# SimpleFOCShieldV3_SchDoc_2024-06-23.net
KiCad netlist of a schematic drawn in Altium Designer
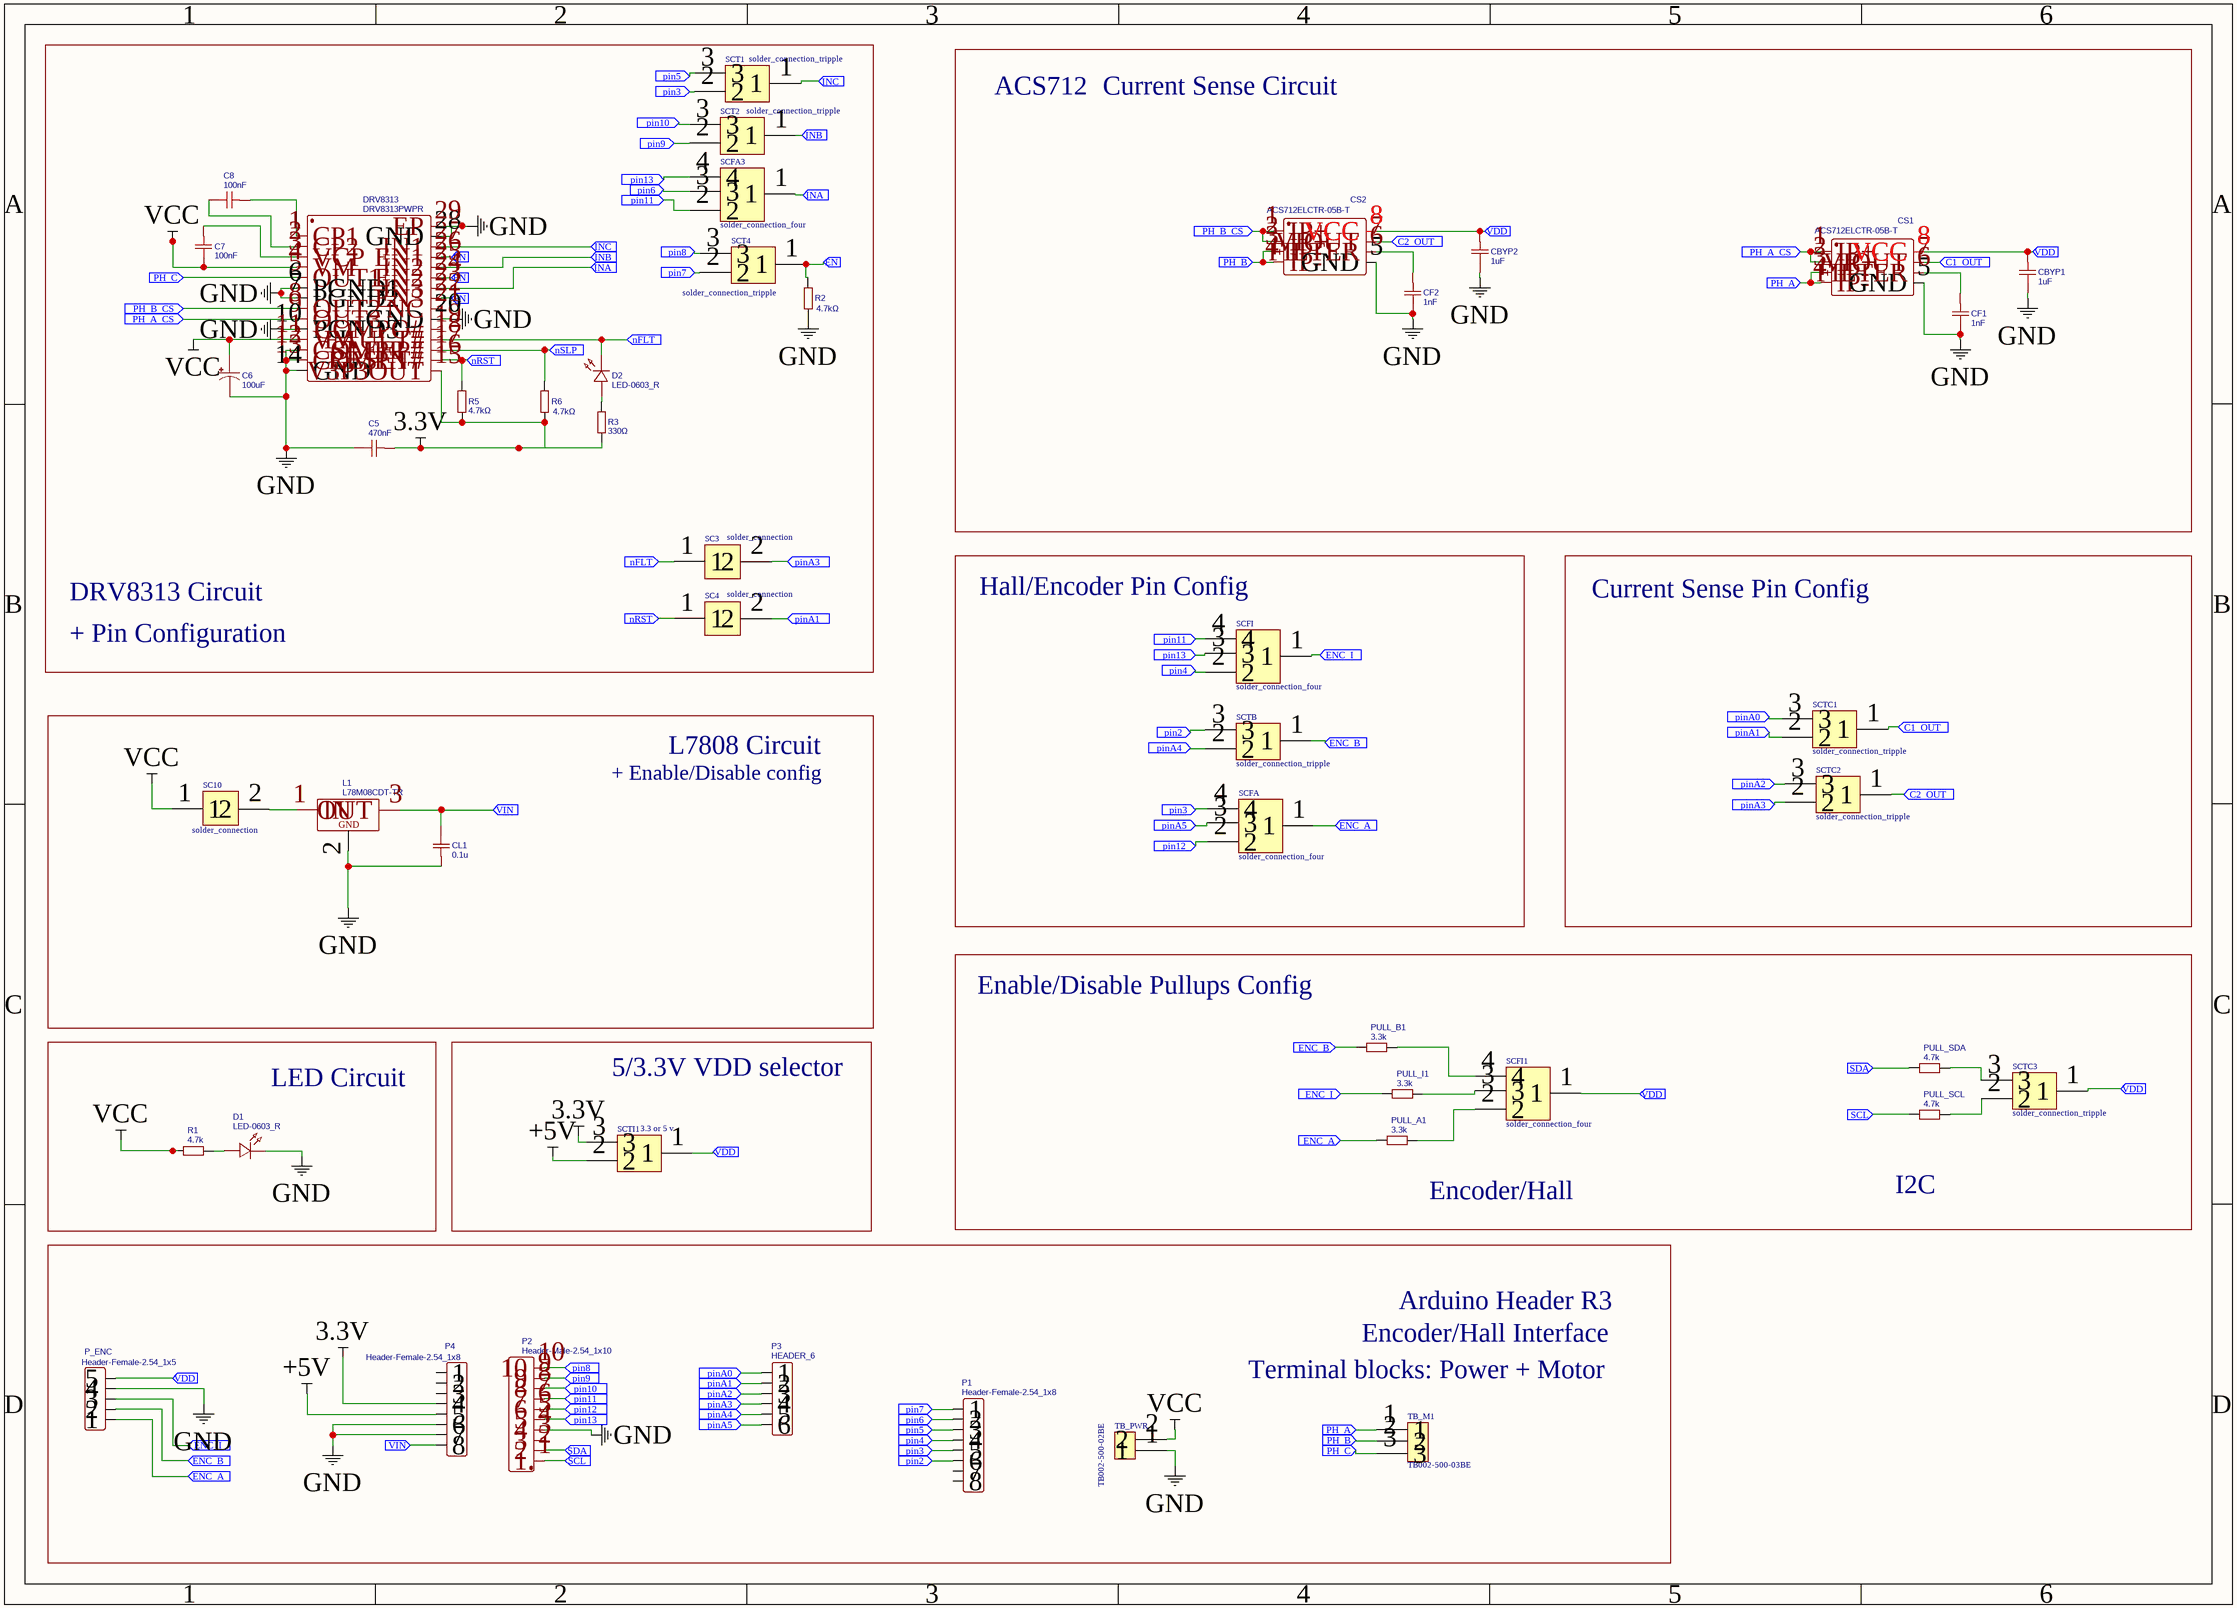
[diagram p0: SimpleFOCShieldV3.SchDoc_2024-06-23.schdoc]

(export (version "E")
  (design (tool "Eeschema 10.0.6"))
  (components
    (comp (ref "C5")
      (value "470nF")
      (fields
        (field (name "MANUFACTURER") "YAGEO")
        (field (name "MANUFACTURER PART") "CC0603ZRY5V6BB474")
        (field (name "CONTRIBUTOR") "LCSC")
      )
      (libsource (lib "altium-import") (part "root_0_470nF_"))
    )
    (comp (ref "C6")
      (value "100uF")
      (fields
        (field (name "MANUFACTURER") "Vertical Technology")
        (field (name "MANUFACTURER PART") "VT1V101M-CRE77")
        (field (name "CONTRIBUTOR") "LCSC")
      )
      (libsource (lib "altium-import") (part "root_0_100uF_"))
    )
    (comp (ref "C7")
      (value "100nF")
      (fields (field (name "MANUFACTURER") "SAMSUNG") (field (name "MANUFACTURER PART") "CL10B104KB8NNNC"))
      (libsource (lib "altium-import") (part "root_1_100nF_"))
    )
    (comp (ref "C8")
      (value "100nF")
      (fields (field (name "MANUFACTURER") "SAMSUNG") (field (name "MANUFACTURER PART") "CL10B104KB8NNNC"))
      (libsource (lib "altium-import") (part "root_0_100nF_"))
    )
    (comp (ref "CBYP1")
      (value "1uF")
      (fields (field (name "CONTRIBUTOR") "LCEDA_Lib"))
      (libsource (lib "altium-import") (part "root_1_1uF_"))
    )
    (comp (ref "CBYP2")
      (value "1uF")
      (fields (field (name "CONTRIBUTOR") "LCEDA_Lib"))
      (libsource (lib "altium-import") (part "root_1_1uF_"))
    )
    (comp (ref "CF1")
      (value "1nF")
      (fields (field (name "CONTRIBUTOR") "LCEDA_Lib"))
      (libsource (lib "altium-import") (part "root_1_1nF_"))
    )
    (comp (ref "CF2")
      (value "1nF")
      (fields (field (name "CONTRIBUTOR") "LCEDA_Lib"))
      (libsource (lib "altium-import") (part "root_1_1nF_"))
    )
    (comp (ref "CL1")
      (value "0.1u")
      (fields (field (name "CONTRIBUTOR") "LCEDA_Lib"))
      (libsource (lib "altium-import") (part "root_3_0.1u_"))
    )
    (comp (ref "CS1")
      (value "ACS712ELCTR-05B-T")
      (fields (field (name "MANUFACTURER") "ALLEGRO(美国埃戈罗)"))
      (libsource (lib "altium-import") (part "root_0_ACS712ELCTR-05B-T_"))
    )
    (comp (ref "CS2")
      (value "ACS712ELCTR-05B-T")
      (fields (field (name "MANUFACTURER") "ALLEGRO(美国埃戈罗)"))
      (libsource (lib "altium-import") (part "root_0_ACS712ELCTR-05B-T_"))
    )
    (comp (ref "D1")
      (value "LED-0603_R")
      (fields
        (field (name "MANUFACTURER") "EVERLIGHT(台湾亿光)")
        (field (name "MANUFACTURER PART") "19-217/R6C-AL1M2VY/3T")
        (field (name "CONTRIBUTOR") "LCEDA_01")
      )
      (libsource (lib "altium-import") (part "root_0_LED-0603_R_"))
    )
    (comp (ref "D2")
      (value "LED-0603_R")
      (fields
        (field (name "MANUFACTURER") "EVERLIGHT(台湾亿光)")
        (field (name "MANUFACTURER PART") "19-217/R6C-AL1M2VY/3T")
        (field (name "CONTRIBUTOR") "LCEDA_01")
      )
      (libsource (lib "altium-import") (part "root_1_LED-0603_R_"))
    )
    (comp (ref "DRV8313")
      (value "DRV8313PWPR")
      (fields (field (name "MANUFACTURER") "Texas Instruments") (field (name "CONTRIBUTOR") "LCSC"))
      (libsource (lib "altium-import") (part "root_0_DRV8313PWPR_"))
    )
    (comp (ref "L1")
      (value "L78M08CDT-TR")
      (fields (field (name "MANUFACTURER") "STMicroelectronics") (field (name "CONTRIBUTOR") "LCSC"))
      (libsource (lib "altium-import") (part "root_0_L78M08CDT-TR_"))
    )
    (comp (ref "P1")
      (value "Header-Female-2.54_1x8")
      (fields
        (field (name "MANUFACTURER") "BOOMELE")
        (field (name "MANUFACTURER PART") "Female headerHDR1X8-2.54")
      )
      (libsource (lib "altium-import") (part "root_0_Header-Female-2.54_1x8_"))
    )
    (comp (ref "P2")
      (value "Header-Male-2.54_1x10")
      (fields (field (name "MANUFACTURER PART") "Headers  Pins2.54mm1*10P"))
      (libsource (lib "altium-import") (part "root_2_Header-Male-2.54_1x10_"))
    )
    (comp (ref "P3") (value "HEADER_6") (libsource (lib "altium-import") (part "root_0_HEADER_6_")))
    (comp (ref "P4")
      (value "Header-Female-2.54_1x8")
      (fields
        (field (name "MANUFACTURER") "BOOMELE")
        (field (name "MANUFACTURER PART") "Female headerHDR1X8-2.54")
      )
      (libsource (lib "altium-import") (part "root_0_Header-Female-2.54_1x8_"))
    )
    (comp (ref "PULL_A1") (value "3.3k") (libsource (lib "altium-import") (part "root_2_3.3k_")))
    (comp (ref "PULL_B1") (value "3.3k") (libsource (lib "altium-import") (part "root_2_3.3k_")))
    (comp (ref "PULL_I1") (value "3.3k") (libsource (lib "altium-import") (part "root_2_3.3k_")))
    (comp (ref "PULL_SCL")
      (value "4.7k")
      (fields (field (name "MANUFACTURER") "UniOhm") (field (name "MANUFACTURER PART") "0603WAF4701T5E"))
      (libsource (lib "altium-import") (part "root_2_4.7k_"))
    )
    (comp (ref "PULL_SDA")
      (value "4.7k")
      (fields (field (name "MANUFACTURER") "UniOhm") (field (name "MANUFACTURER PART") "0603WAF4701T5E"))
      (libsource (lib "altium-import") (part "root_2_4.7k_"))
    )
    (comp (ref "P_ENC")
      (value "Header-Female-2.54_1x5")
      (fields
        (field (name "MANUFACTURER") "BOOMELE")
        (field (name "MANUFACTURER PART") "2.54mm 1*5p Female header")
      )
      (libsource (lib "altium-import") (part "root_2_Header-Female-2.54_1x5_"))
    )
    (comp (ref "R1")
      (value "4.7k")
      (fields (field (name "MANUFACTURER") "UniOhm") (field (name "MANUFACTURER PART") "0603WAF4701T5E"))
      (libsource (lib "altium-import") (part "root_2_4.7k_"))
    )
    (comp (ref "R2")
      (value "4.7kΩ")
      (fields (field (name "MANUFACTURER") "UniOhm") (field (name "MANUFACTURER PART") "0603WAF4701T5E"))
      (libsource (lib "altium-import") (part "root_1_4.7kΩ_"))
    )
    (comp (ref "R3") (value "330Ω") (libsource (lib "altium-import") (part "root_1_330Ω_")))
    (comp (ref "R5")
      (value "4.7kΩ")
      (fields (field (name "MANUFACTURER") "UniOhm") (field (name "MANUFACTURER PART") "0603WAF4701T5E"))
      (libsource (lib "altium-import") (part "root_1_4.7kΩ_"))
    )
    (comp (ref "R6")
      (value "4.7kΩ")
      (fields (field (name "MANUFACTURER") "UniOhm") (field (name "MANUFACTURER PART") "0603WAF4701T5E"))
      (libsource (lib "altium-import") (part "root_1_4.7kΩ_"))
    )
    (comp (ref "SC3") (value "solder_connection") (libsource (lib "") (part "root_0_solder_connection__1")))
    (comp (ref "SC4") (value "solder_connection") (libsource (lib "") (part "root_0_solder_connection__1")))
    (comp (ref "SC10")
      (value "solder_connection")
      (libsource (lib "altium-import") (part "root_0_solder_connection_"))
    )
    (comp (ref "SCFA")
      (value "solder_connection_four")
      (libsource (lib "") (part "root_2_solder_connection_four__2"))
    )
    (comp (ref "SCFA3")
      (value "solder_connection_four")
      (libsource (lib "altium-import") (part "root_2_solder_connection_four_"))
    )
    (comp (ref "SCFI")
      (value "solder_connection_four")
      (libsource (lib "") (part "root_2_solder_connection_four__1"))
    )
    (comp (ref "SCFI1")
      (value "solder_connection_four")
      (libsource (lib "") (part "root_2_solder_connection_four__1"))
    )
    (comp (ref "SCT1")
      (value "solder_connection_tripple")
      (libsource (lib "") (part "root_2_solder_connection_tripple__5"))
    )
    (comp (ref "SCT2")
      (value "solder_connection_tripple")
      (libsource (lib "") (part "root_2_solder_connection_tripple__2"))
    )
    (comp (ref "SCT4")
      (value "solder_connection_tripple")
      (libsource (lib "") (part "root_2_solder_connection_tripple__3"))
    )
    (comp (ref "SCTB")
      (value "solder_connection_tripple")
      (libsource (lib "") (part "root_2_solder_connection_tripple__4"))
    )
    (comp (ref "SCTC1")
      (value "solder_connection_tripple")
      (libsource (lib "altium-import") (part "root_2_solder_connection_tripple_"))
    )
    (comp (ref "SCTC2")
      (value "solder_connection_tripple")
      (libsource (lib "") (part "root_2_solder_connection_tripple__1"))
    )
    (comp (ref "SCTC3")
      (value "solder_connection_tripple")
      (libsource (lib "") (part "root_2_solder_connection_tripple__1"))
    )
    (comp (ref "SCTI1") (value "3.3 or 5 v") (libsource (lib "altium-import") (part "root_2_3.3 or 5 v_")))
    (comp (ref "TB_M1")
      (value "TB002-500-03BE")
      (libsource (lib "altium-import") (part "root_2_TB002-500-03BE_"))
    )
    (comp (ref "TB_PWR")
      (value "TB002-500-02BE")
      (libsource (lib "altium-import") (part "root_0_TB002-500-02BE_"))
    )
  )
  (nets
    (net (code "1") (name "+5V") (class "Default")
      (node (ref "P4") (pin "5") (pinfunction "5_5") (pintype "passive"))
      (node (ref "SCTI1") (pin "2") (pinfunction "2_2") (pintype "passive"))
    )
    (net (code "2") (name "/C1_OUT") (class "Default")
      (node (ref "CS1") (pin "7") (pinfunction "VIOUT_7") (pintype "passive"))
      (node (ref "SCTC1") (pin "1") (pinfunction "1_1") (pintype "passive"))
    )
    (net (code "3") (name "/C2_OUT") (class "Default")
      (node (ref "CS2") (pin "7") (pinfunction "VIOUT_7") (pintype "passive"))
      (node (ref "SCTC2") (pin "1") (pinfunction "1_1") (pintype "passive"))
    )
    (net (code "4") (name "/EN") (class "Default")
      (node (ref "DRV8313") (pin "22") (pinfunction "EN3_22") (pintype "passive"))
      (node (ref "DRV8313") (pin "24") (pinfunction "EN2_24") (pintype "passive"))
      (node (ref "DRV8313") (pin "26") (pinfunction "EN1_26") (pintype "passive"))
      (node (ref "R2") (pin "2") (pinfunction "2_2") (pintype "passive"))
      (node (ref "SCT4") (pin "1") (pinfunction "1_1") (pintype "passive"))
    )
    (net (code "5") (name "/ENC_A") (class "Default")
      (node (ref "PULL_A1") (pin "2") (pinfunction "2_2") (pintype "passive"))
      (node (ref "P_ENC") (pin "1") (pinfunction "1_1") (pintype "passive"))
      (node (ref "SCFA") (pin "1") (pinfunction "1_1") (pintype "passive"))
    )
    (net (code "6") (name "/ENC_B") (class "Default")
      (node (ref "PULL_B1") (pin "2") (pinfunction "2_2") (pintype "passive"))
      (node (ref "P_ENC") (pin "2") (pinfunction "2_2") (pintype "passive"))
      (node (ref "SCTB") (pin "1") (pinfunction "1_1") (pintype "passive"))
    )
    (net (code "7") (name "/ENC_I") (class "Default")
      (node (ref "PULL_I1") (pin "2") (pinfunction "2_2") (pintype "passive"))
      (node (ref "P_ENC") (pin "3") (pinfunction "3_3") (pintype "passive"))
      (node (ref "SCFI") (pin "1") (pinfunction "1_1") (pintype "passive"))
    )
    (net (code "8") (name "/INA") (class "Default")
      (node (ref "DRV8313") (pin "23") (pinfunction "IN3_23") (pintype "passive"))
      (node (ref "SCFA3") (pin "1") (pinfunction "1_1") (pintype "passive"))
    )
    (net (code "9") (name "/INB") (class "Default")
      (node (ref "DRV8313") (pin "25") (pinfunction "IN2_25") (pintype "passive"))
      (node (ref "SCT2") (pin "1") (pinfunction "1_1") (pintype "passive"))
    )
    (net (code "10") (name "/INC") (class "Default")
      (node (ref "DRV8313") (pin "27") (pinfunction "IN1_27") (pintype "passive"))
      (node (ref "SCT1") (pin "1") (pinfunction "1_1") (pintype "passive"))
    )
    (net (code "11") (name "/PH_A") (class "Default")
      (node (ref "CS1") (pin "3") (pinfunction "IP-_3") (pintype "passive"))
      (node (ref "CS1") (pin "4") (pinfunction "IP-_4") (pintype "passive"))
      (node (ref "TB_M1") (pin "1") (pinfunction "1_1") (pintype "passive"))
    )
    (net (code "12") (name "/PH_A_CS") (class "Default")
      (node (ref "CS1") (pin "1") (pinfunction "IP+_1") (pintype "passive"))
      (node (ref "CS1") (pin "2") (pinfunction "IP+_2") (pintype "passive"))
      (node (ref "DRV8313") (pin "9") (pinfunction "OUT3_9") (pintype "passive"))
    )
    (net (code "13") (name "/PH_B") (class "Default")
      (node (ref "CS2") (pin "3") (pinfunction "IP-_3") (pintype "passive"))
      (node (ref "CS2") (pin "4") (pinfunction "IP-_4") (pintype "passive"))
      (node (ref "TB_M1") (pin "2") (pinfunction "2_2") (pintype "passive"))
    )
    (net (code "14") (name "/PH_B_CS") (class "Default")
      (node (ref "CS2") (pin "1") (pinfunction "IP+_1") (pintype "passive"))
      (node (ref "CS2") (pin "2") (pinfunction "IP+_2") (pintype "passive"))
      (node (ref "DRV8313") (pin "8") (pinfunction "OUT2_8") (pintype "passive"))
    )
    (net (code "15") (name "/PH_C") (class "Default")
      (node (ref "DRV8313") (pin "5") (pinfunction "OUT1_5") (pintype "passive"))
      (node (ref "TB_M1") (pin "3") (pinfunction "3_3") (pintype "passive"))
    )
    (net (code "16") (name "/SCL") (class "Default")
      (node (ref "P2") (pin "1") (pinfunction "1_1") (pintype "passive"))
      (node (ref "PULL_SCL") (pin "2") (pinfunction "2_2") (pintype "passive"))
    )
    (net (code "17") (name "/SDA") (class "Default")
      (node (ref "P2") (pin "2") (pinfunction "2_2") (pintype "passive"))
      (node (ref "PULL_SDA") (pin "2") (pinfunction "2_2") (pintype "passive"))
    )
    (net (code "18") (name "/VDD") (class "Default")
      (node (ref "CBYP1") (pin "2") (pinfunction "2_2") (pintype "passive"))
      (node (ref "CBYP2") (pin "2") (pinfunction "2_2") (pintype "passive"))
      (node (ref "CS1") (pin "8") (pinfunction "VCC_8") (pintype "passive"))
      (node (ref "CS2") (pin "8") (pinfunction "VCC_8") (pintype "passive"))
      (node (ref "P_ENC") (pin "5") (pinfunction "5_5") (pintype "passive"))
      (node (ref "SCFI1") (pin "1") (pinfunction "1_1") (pintype "passive"))
      (node (ref "SCTC3") (pin "1") (pinfunction "1_1") (pintype "passive"))
      (node (ref "SCTI1") (pin "1") (pinfunction "1_1") (pintype "passive"))
    )
    (net (code "19") (name "/VIN") (class "Default")
      (node (ref "CL1") (pin "1") (pinfunction "1_1") (pintype "passive"))
      (node (ref "L1") (pin "3") (pinfunction "OUT_3") (pintype "passive"))
      (node (ref "P4") (pin "8") (pinfunction "8_8") (pintype "passive"))
    )
    (net (code "20") (name "/nFLT") (class "Default")
      (node (ref "D2") (pin "2") (pinfunction "2_2") (pintype "passive"))
      (node (ref "DRV8313") (pin "18") (pinfunction "FAULT#_18") (pintype "passive"))
      (node (ref "SC3") (pin "1") (pinfunction "1_1") (pintype "passive"))
    )
    (net (code "21") (name "/nRST") (class "Default")
      (node (ref "DRV8313") (pin "16") (pinfunction "RESET#_16") (pintype "passive"))
      (node (ref "R5") (pin "2") (pinfunction "2_2") (pintype "passive"))
      (node (ref "SC4") (pin "1") (pinfunction "1_1") (pintype "passive"))
    )
    (net (code "22") (name "/nSLP") (class "Default")
      (node (ref "DRV8313") (pin "17") (pinfunction "SLEEP#_17") (pintype "passive"))
      (node (ref "R6") (pin "2") (pinfunction "2_2") (pintype "passive"))
    )
    (net (code "23") (name "/pin2") (class "Default")
      (node (ref "P1") (pin "6") (pinfunction "6_6") (pintype "passive"))
      (node (ref "SCTB") (pin "3") (pinfunction "3_3") (pintype "passive"))
    )
    (net (code "24") (name "/pin3") (class "Default")
      (node (ref "P1") (pin "5") (pinfunction "5_5") (pintype "passive"))
      (node (ref "SCFA") (pin "4") (pinfunction "4_4") (pintype "passive"))
      (node (ref "SCT1") (pin "2") (pinfunction "2_2") (pintype "passive"))
    )
    (net (code "25") (name "/pin4") (class "Default")
      (node (ref "P1") (pin "4") (pinfunction "4_4") (pintype "passive"))
      (node (ref "SCFI") (pin "2") (pinfunction "2_2") (pintype "passive"))
    )
    (net (code "26") (name "/pin5") (class "Default")
      (node (ref "P1") (pin "3") (pinfunction "3_3") (pintype "passive"))
      (node (ref "SCT1") (pin "3") (pinfunction "3_3") (pintype "passive"))
    )
    (net (code "27") (name "/pin6") (class "Default")
      (node (ref "P1") (pin "2") (pinfunction "2_2") (pintype "passive"))
      (node (ref "SCFA3") (pin "3") (pinfunction "3_3") (pintype "passive"))
    )
    (net (code "28") (name "/pin7") (class "Default")
      (node (ref "P1") (pin "1") (pinfunction "1_1") (pintype "passive"))
      (node (ref "SCT4") (pin "2") (pinfunction "2_2") (pintype "passive"))
    )
    (net (code "29") (name "/pin8") (class "Default")
      (node (ref "P2") (pin "10") (pinfunction "10_10") (pintype "passive"))
      (node (ref "SCT4") (pin "3") (pinfunction "3_3") (pintype "passive"))
    )
    (net (code "30") (name "/pin9") (class "Default")
      (node (ref "P2") (pin "9") (pinfunction "9_9") (pintype "passive"))
      (node (ref "SCT2") (pin "2") (pinfunction "2_2") (pintype "passive"))
    )
    (net (code "31") (name "/pin10") (class "Default")
      (node (ref "P2") (pin "8") (pinfunction "8_8") (pintype "passive"))
      (node (ref "SCT2") (pin "3") (pinfunction "3_3") (pintype "passive"))
    )
    (net (code "32") (name "/pin11") (class "Default")
      (node (ref "P2") (pin "7") (pinfunction "7_7") (pintype "passive"))
      (node (ref "SCFA3") (pin "2") (pinfunction "2_2") (pintype "passive"))
      (node (ref "SCFI") (pin "4") (pinfunction "4_4") (pintype "passive"))
    )
    (net (code "33") (name "/pin12") (class "Default")
      (node (ref "P2") (pin "6") (pinfunction "6_6") (pintype "passive"))
      (node (ref "SCFA") (pin "2") (pinfunction "2_2") (pintype "passive"))
    )
    (net (code "34") (name "/pin13") (class "Default")
      (node (ref "P2") (pin "5") (pinfunction "5_5") (pintype "passive"))
      (node (ref "SCFA3") (pin "4") (pinfunction "4_4") (pintype "passive"))
      (node (ref "SCFI") (pin "3") (pinfunction "3_3") (pintype "passive"))
    )
    (net (code "35") (name "/pinA0") (class "Default")
      (node (ref "P3") (pin "1") (pinfunction "1_1") (pintype "passive"))
      (node (ref "SCTC1") (pin "3") (pinfunction "3_3") (pintype "passive"))
    )
    (net (code "36") (name "/pinA1") (class "Default")
      (node (ref "P3") (pin "2") (pinfunction "2_2") (pintype "passive"))
      (node (ref "SC4") (pin "2") (pinfunction "2_2") (pintype "passive"))
      (node (ref "SCTC1") (pin "2") (pinfunction "2_2") (pintype "passive"))
    )
    (net (code "37") (name "/pinA2") (class "Default")
      (node (ref "P3") (pin "3") (pinfunction "3_3") (pintype "passive"))
      (node (ref "SCTC2") (pin "3") (pinfunction "3_3") (pintype "passive"))
    )
    (net (code "38") (name "/pinA3") (class "Default")
      (node (ref "P3") (pin "4") (pinfunction "4_4") (pintype "passive"))
      (node (ref "SC3") (pin "2") (pinfunction "2_2") (pintype "passive"))
      (node (ref "SCTC2") (pin "2") (pinfunction "2_2") (pintype "passive"))
    )
    (net (code "39") (name "/pinA4") (class "Default")
      (node (ref "P3") (pin "5") (pinfunction "5_5") (pintype "passive"))
      (node (ref "SCTB") (pin "2") (pinfunction "2_2") (pintype "passive"))
    )
    (net (code "40") (name "/pinA5") (class "Default")
      (node (ref "P3") (pin "6") (pinfunction "6_6") (pintype "passive"))
      (node (ref "SCFA") (pin "3") (pinfunction "3_3") (pintype "passive"))
    )
    (net (code "41") (name "3.3V") (class "Default")
      (node (ref "C5") (pin "2") (pinfunction "2_2") (pintype "passive"))
      (node (ref "DRV8313") (pin "15") (pinfunction "V3P3OUT_15") (pintype "passive"))
      (node (ref "P4") (pin "4") (pinfunction "4_4") (pintype "passive"))
      (node (ref "R3") (pin "1") (pinfunction "1_1") (pintype "passive"))
      (node (ref "R5") (pin "1") (pinfunction "1_1") (pintype "passive"))
      (node (ref "R6") (pin "1") (pinfunction "1_1") (pintype "passive"))
      (node (ref "SCTI1") (pin "3") (pinfunction "3_3") (pintype "passive"))
    )
    (net (code "42") (name "GND") (class "Default")
      (node (ref "C5") (pin "1") (pinfunction "1_1") (pintype "passive"))
      (node (ref "C6") (pin "2") (pinfunction "2_2") (pintype "passive"))
      (node (ref "CBYP1") (pin "1") (pinfunction "1_1") (pintype "passive"))
      (node (ref "CBYP2") (pin "1") (pinfunction "1_1") (pintype "passive"))
      (node (ref "CF1") (pin "1") (pinfunction "1_1") (pintype "passive"))
      (node (ref "CF2") (pin "1") (pinfunction "1_1") (pintype "passive"))
      (node (ref "CL1") (pin "2") (pinfunction "2_2") (pintype "passive"))
      (node (ref "CS1") (pin "5") (pinfunction "GND_5") (pintype "passive"))
      (node (ref "CS2") (pin "5") (pinfunction "GND_5") (pintype "passive"))
      (node (ref "D1") (pin "2") (pinfunction "2_2") (pintype "passive"))
      (node (ref "DRV8313") (pin "10") (pinfunction "PGND3_10") (pintype "passive"))
      (node (ref "DRV8313") (pin "12") (pinfunction "COMPP_12") (pintype "passive"))
      (node (ref "DRV8313") (pin "13") (pinfunction "COMPN_13") (pintype "passive"))
      (node (ref "DRV8313") (pin "14") (pinfunction "GND_14") (pintype "passive"))
      (node (ref "DRV8313") (pin "20") (pinfunction "GND_20") (pintype "passive"))
      (node (ref "DRV8313") (pin "28") (pinfunction "GND_28") (pintype "passive"))
      (node (ref "DRV8313") (pin "29") (pinfunction "EP_29") (pintype "passive"))
      (node (ref "DRV8313") (pin "6") (pinfunction "PGND1_6") (pintype "passive"))
      (node (ref "DRV8313") (pin "7") (pinfunction "PGND2_7") (pintype "passive"))
      (node (ref "L1") (pin "2") (pinfunction "GND_2") (pintype "passive"))
      (node (ref "P2") (pin "4") (pinfunction "4_4") (pintype "passive"))
      (node (ref "P4") (pin "6") (pinfunction "6_6") (pintype "passive"))
      (node (ref "P4") (pin "7") (pinfunction "7_7") (pintype "passive"))
      (node (ref "P_ENC") (pin "4") (pinfunction "4_4") (pintype "passive"))
      (node (ref "R2") (pin "1") (pinfunction "1_1") (pintype "passive"))
      (node (ref "TB_PWR") (pin "1") (pinfunction "1_1") (pintype "passive"))
    )
    (net (code "43") (name "Net-(CS1-FILTER)") (class "Default")
      (node (ref "CF1") (pin "2") (pinfunction "2_2") (pintype "passive"))
      (node (ref "CS1") (pin "6") (pinfunction "FILTER_6") (pintype "passive"))
    )
    (net (code "44") (name "Net-(CS2-FILTER)") (class "Default")
      (node (ref "CF2") (pin "2") (pinfunction "2_2") (pintype "passive"))
      (node (ref "CS2") (pin "6") (pinfunction "FILTER_6") (pintype "passive"))
    )
    (net (code "45") (name "Net-(D1-Pad1)") (class "Default")
      (node (ref "D1") (pin "1") (pinfunction "1_1") (pintype "passive"))
      (node (ref "R1") (pin "1") (pinfunction "1_1") (pintype "passive"))
    )
    (net (code "46") (name "Net-(D2-Pad1)") (class "Default")
      (node (ref "D2") (pin "1") (pinfunction "1_1") (pintype "passive"))
      (node (ref "R3") (pin "2") (pinfunction "2_2") (pintype "passive"))
    )
    (net (code "47") (name "Net-(DRV8313-CP1)") (class "Default")
      (node (ref "C8") (pin "2") (pinfunction "2_2") (pintype "passive"))
      (node (ref "DRV8313") (pin "1") (pinfunction "CP1_1") (pintype "passive"))
    )
    (net (code "48") (name "Net-(DRV8313-CP2)") (class "Default")
      (node (ref "C8") (pin "1") (pinfunction "1_1") (pintype "passive"))
      (node (ref "DRV8313") (pin "2") (pinfunction "CP2_2") (pintype "passive"))
    )
    (net (code "49") (name "Net-(DRV8313-VCP)") (class "Default")
      (node (ref "C7") (pin "2") (pinfunction "2_2") (pintype "passive"))
      (node (ref "DRV8313") (pin "3") (pinfunction "VCP_3") (pintype "passive"))
    )
    (net (code "50") (name "Net-(L1-IN)") (class "Default")
      (node (ref "L1") (pin "1") (pinfunction "IN_1") (pintype "passive"))
      (node (ref "SC10") (pin "2") (pinfunction "2_2") (pintype "passive"))
    )
    (net (code "51") (name "Net-(PULL_A1-Pad1)") (class "Default")
      (node (ref "PULL_A1") (pin "1") (pinfunction "1_1") (pintype "passive"))
      (node (ref "SCFI1") (pin "2") (pinfunction "2_2") (pintype "passive"))
    )
    (net (code "52") (name "Net-(PULL_B1-Pad1)") (class "Default")
      (node (ref "PULL_B1") (pin "1") (pinfunction "1_1") (pintype "passive"))
      (node (ref "SCFI1") (pin "4") (pinfunction "4_4") (pintype "passive"))
    )
    (net (code "53") (name "Net-(PULL_I1-Pad1)") (class "Default")
      (node (ref "PULL_I1") (pin "1") (pinfunction "1_1") (pintype "passive"))
      (node (ref "SCFI1") (pin "3") (pinfunction "3_3") (pintype "passive"))
    )
    (net (code "54") (name "Net-(PULL_SCL-Pad1)") (class "Default")
      (node (ref "PULL_SCL") (pin "1") (pinfunction "1_1") (pintype "passive"))
      (node (ref "SCTC3") (pin "2") (pinfunction "2_2") (pintype "passive"))
    )
    (net (code "55") (name "Net-(PULL_SDA-Pad1)") (class "Default")
      (node (ref "PULL_SDA") (pin "1") (pinfunction "1_1") (pintype "passive"))
      (node (ref "SCTC3") (pin "3") (pinfunction "3_3") (pintype "passive"))
    )
    (net (code "56") (name "VCC") (class "Default")
      (node (ref "C6") (pin "1") (pinfunction "1_1") (pintype "passive"))
      (node (ref "C7") (pin "1") (pinfunction "1_1") (pintype "passive"))
      (node (ref "DRV8313") (pin "11") (pinfunction "VM_11") (pintype "passive"))
      (node (ref "DRV8313") (pin "4") (pinfunction "VM_4") (pintype "passive"))
      (node (ref "R1") (pin "2") (pinfunction "2_2") (pintype "passive"))
      (node (ref "SC10") (pin "1") (pinfunction "1_1") (pintype "passive"))
      (node (ref "TB_PWR") (pin "2") (pinfunction "2_2") (pintype "passive"))
    )
    (net (code "57") (name "unconnected-(DRV8313-COMPO#-Pad19)") (class "Default")
      (node (ref "DRV8313") (pin "19") (pinfunction "COMPO#_19") (pintype "passive"))
    )
    (net (code "58") (name "unconnected-(DRV8313-NC-Pad21)") (class "Default")
      (node (ref "DRV8313") (pin "21") (pinfunction "NC_21") (pintype "passive"))
    )
    (net (code "59") (name "unconnected-(P1-Pad7)") (class "Default")
      (node (ref "P1") (pin "7") (pinfunction "7_7") (pintype "passive"))
    )
    (net (code "60") (name "unconnected-(P1-Pad8)") (class "Default")
      (node (ref "P1") (pin "8") (pinfunction "8_8") (pintype "passive"))
    )
    (net (code "61") (name "unconnected-(P2-Pad3)") (class "Default")
      (node (ref "P2") (pin "3") (pinfunction "3_3") (pintype "passive"))
    )
    (net (code "62") (name "unconnected-(P4-Pad1)") (class "Default")
      (node (ref "P4") (pin "1") (pinfunction "1_1") (pintype "passive"))
    )
    (net (code "63") (name "unconnected-(P4-Pad2)") (class "Default")
      (node (ref "P4") (pin "2") (pinfunction "2_2") (pintype "passive"))
    )
    (net (code "64") (name "unconnected-(P4-Pad3)") (class "Default")
      (node (ref "P4") (pin "3") (pinfunction "3_3") (pintype "passive"))
    )
  )
)
